# Microcontroller.net
KiCad netlist of a schematic drawn in Altium Designer
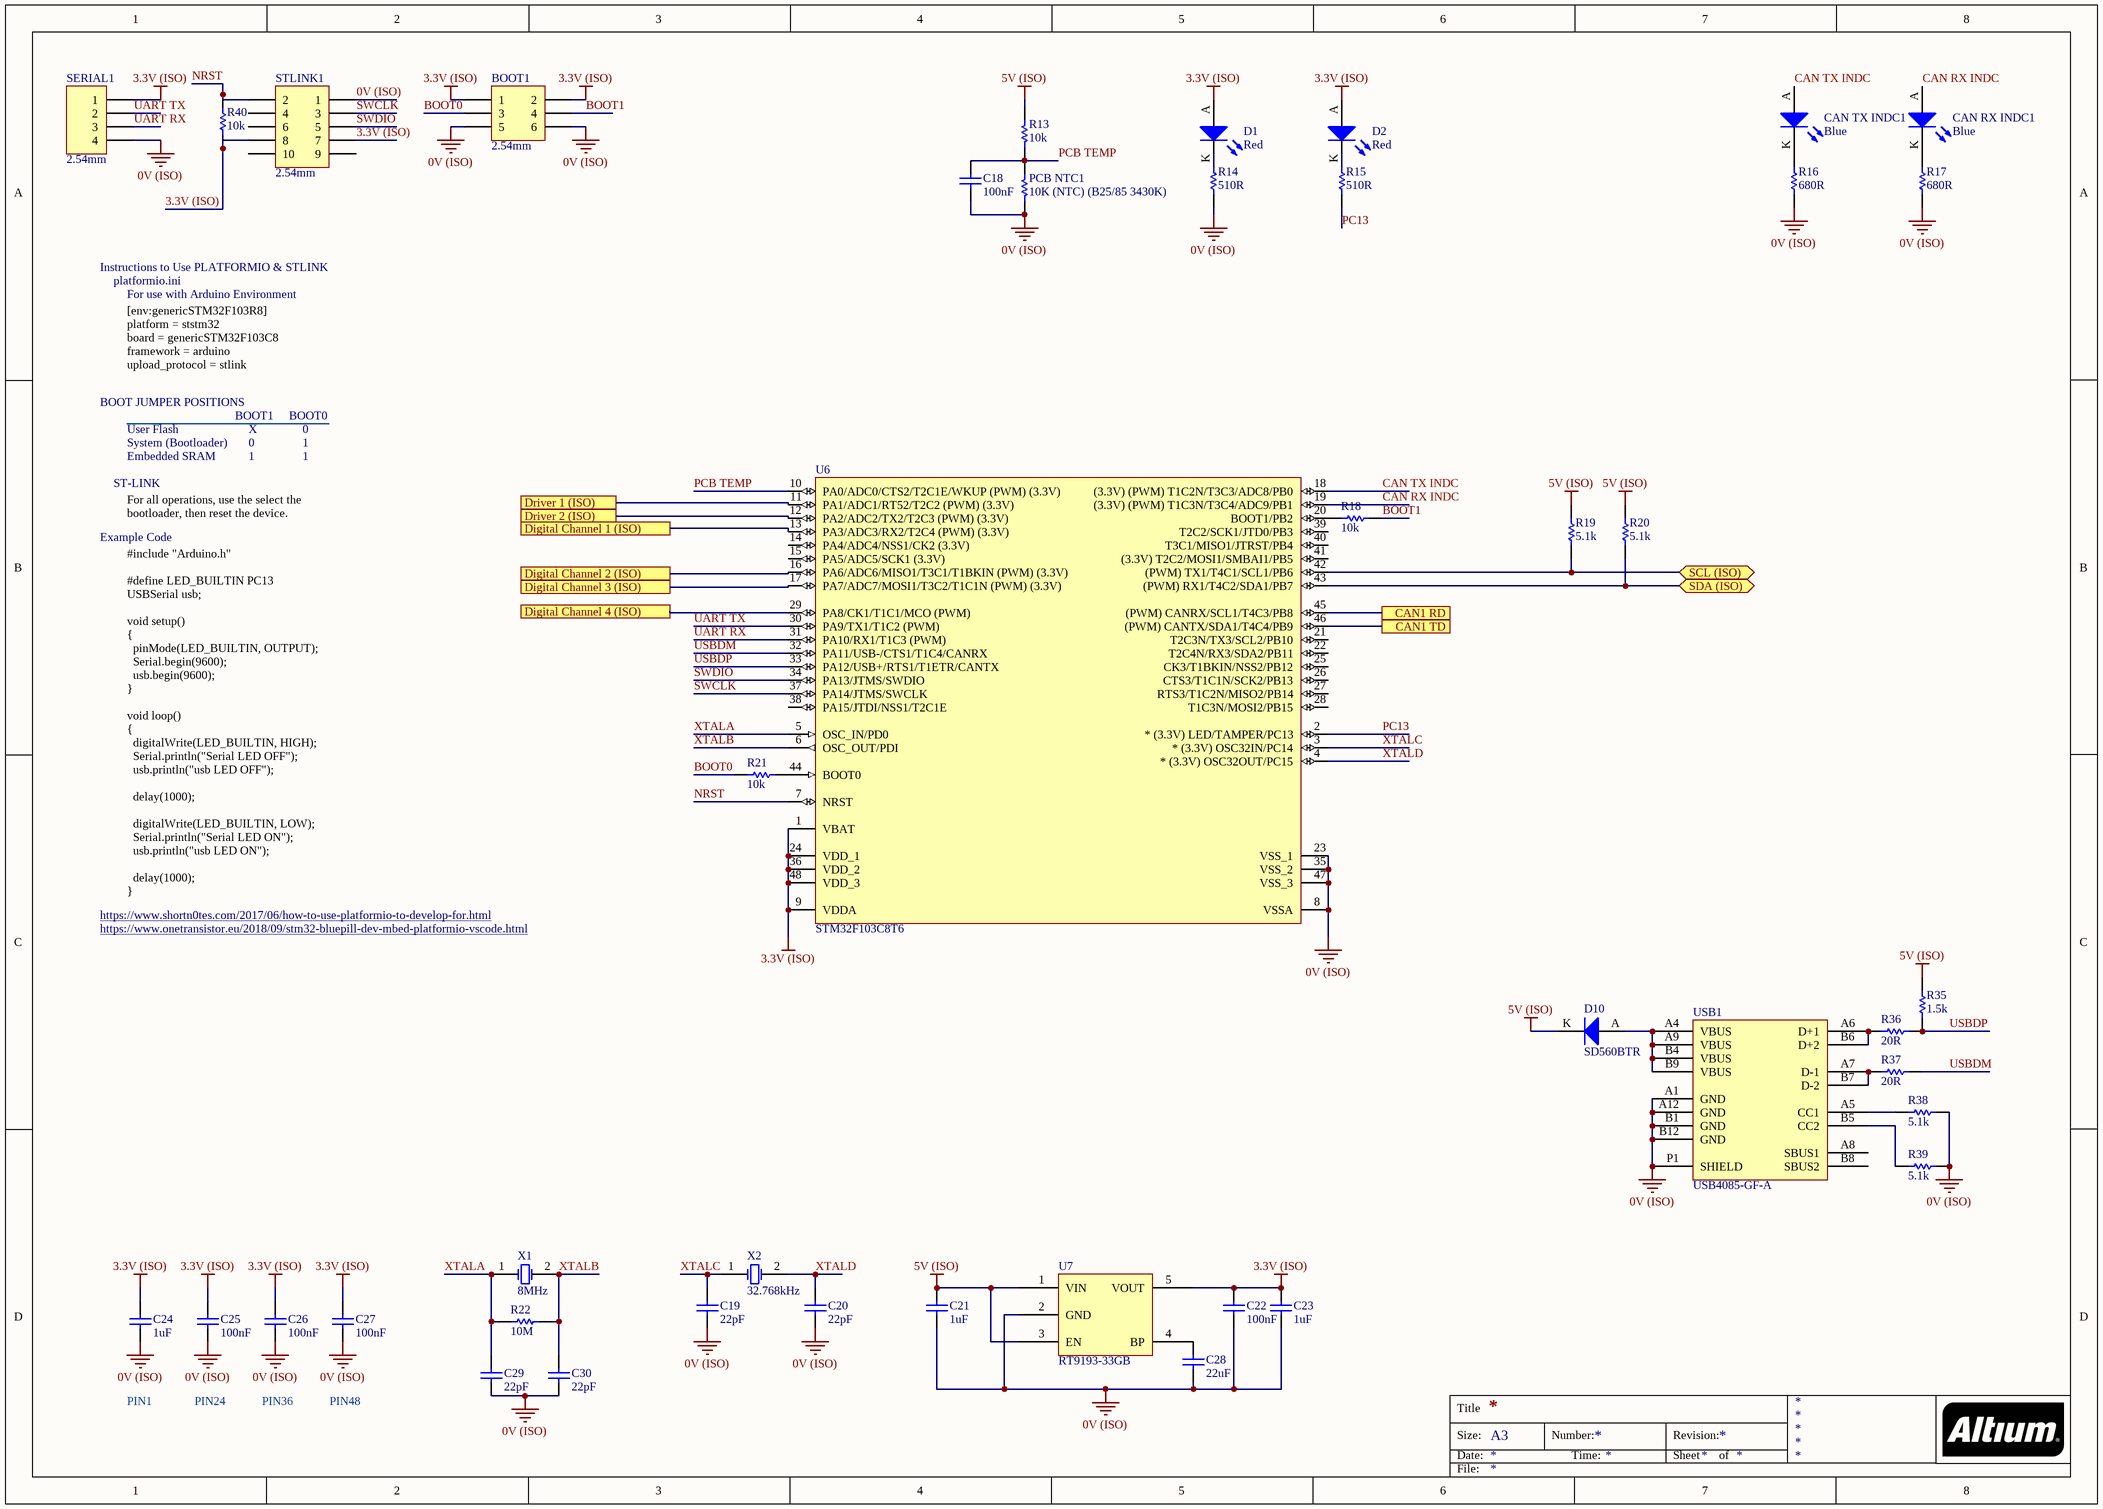
[diagram p0: Microcontroller.SchDoc]

(export (version "E")
  (design (tool "Eeschema 10.0.6"))
  (components
    (comp (ref "BOOT1")
      (value "2.54mm")
      (footprint "TH 2.54mm Header 2x3")
      (fields (field (name "PART NUMBER") "TH 2.54mm Header 2x3") (field (name "CONTACT") "NA"))
      (libsource (lib "ts_20-standard-connectors") (part "Header 2x3"))
    )
    (comp (ref "C18")
      (value "100nF")
      (footprint "0805")
      (fields
        (field (name "PART NUMBER") "GCM21BR71E104KA37L")
        (field (name "TOLERANCE") "10%")
        (field (name "MANUFACTURER") "muRata")
      )
      (libsource (lib "ts_20-standard-library") (part "Capacitor"))
    )
    (comp (ref "C19")
      (value "22pF")
      (footprint "0805")
      (fields
        (field (name "PART NUMBER") "GCM21B5C1H220JA37L")
        (field (name "TOLERANCE") "5%")
        (field (name "MANUFACTURER") "muRata")
      )
      (libsource (lib "ts_20-standard-library") (part "Capacitor"))
    )
    (comp (ref "C20")
      (value "22pF")
      (footprint "0805")
      (fields
        (field (name "PART NUMBER") "GCM21B5C1H220JA37L")
        (field (name "TOLERANCE") "5%")
        (field (name "MANUFACTURER") "muRata")
      )
      (libsource (lib "ts_20-standard-library") (part "Capacitor"))
    )
    (comp (ref "C21")
      (value "1uF")
      (footprint "0805")
      (fields
        (field (name "PART NUMBER") "AC0805KKX7R8BB105")
        (field (name "TOLERANCE") "10%")
        (field (name "MANUFACTURER") "YAGEO")
      )
      (libsource (lib "ts_20-standard-library") (part "Capacitor"))
    )
    (comp (ref "C22")
      (value "100nF")
      (footprint "0805")
      (fields
        (field (name "PART NUMBER") "GCM21BR71E104KA37L")
        (field (name "TOLERANCE") "10%")
        (field (name "MANUFACTURER") "muRata")
      )
      (libsource (lib "ts_20-standard-library") (part "Capacitor"))
    )
    (comp (ref "C23")
      (value "1uF")
      (footprint "0805")
      (fields
        (field (name "PART NUMBER") "AC0805KKX7R8BB105")
        (field (name "TOLERANCE") "10%")
        (field (name "MANUFACTURER") "YAGEO")
      )
      (libsource (lib "ts_20-standard-library") (part "Capacitor"))
    )
    (comp (ref "C24")
      (value "1uF")
      (footprint "0805")
      (fields
        (field (name "PART NUMBER") "AC0805KKX7R8BB105")
        (field (name "TOLERANCE") "10%")
        (field (name "MANUFACTURER") "YAGEO")
      )
      (libsource (lib "ts_20-standard-library") (part "Capacitor"))
    )
    (comp (ref "C25")
      (value "100nF")
      (footprint "0805")
      (fields
        (field (name "PART NUMBER") "GCM21BR71E104KA37L")
        (field (name "TOLERANCE") "10%")
        (field (name "MANUFACTURER") "muRata")
      )
      (libsource (lib "ts_20-standard-library") (part "Capacitor"))
    )
    (comp (ref "C26")
      (value "100nF")
      (footprint "0805")
      (fields
        (field (name "PART NUMBER") "GCM21BR71E104KA37L")
        (field (name "TOLERANCE") "10%")
        (field (name "MANUFACTURER") "muRata")
      )
      (libsource (lib "ts_20-standard-library") (part "Capacitor"))
    )
    (comp (ref "C27")
      (value "100nF")
      (footprint "0805")
      (fields
        (field (name "PART NUMBER") "GCM21BR71E104KA37L")
        (field (name "TOLERANCE") "10%")
        (field (name "MANUFACTURER") "muRata")
      )
      (libsource (lib "ts_20-standard-library") (part "Capacitor"))
    )
    (comp (ref "C28")
      (value "22uF")
      (footprint "0805")
      (fields
        (field (name "PART NUMBER") "GRM21BR61A226ME51L")
        (field (name "TOLERANCE") "20%")
        (field (name "MANUFACTURER") "muRata")
      )
      (libsource (lib "ts_20-standard-library") (part "Capacitor"))
    )
    (comp (ref "C29")
      (value "22pF")
      (footprint "0805")
      (fields
        (field (name "PART NUMBER") "GCM21B5C1H220JA37L")
        (field (name "TOLERANCE") "5%")
        (field (name "MANUFACTURER") "muRata")
      )
      (libsource (lib "ts_20-standard-library") (part "Capacitor"))
    )
    (comp (ref "C30")
      (value "22pF")
      (footprint "0805")
      (fields
        (field (name "PART NUMBER") "GCM21B5C1H220JA37L")
        (field (name "TOLERANCE") "5%")
        (field (name "MANUFACTURER") "muRata")
      )
      (libsource (lib "ts_20-standard-library") (part "Capacitor"))
    )
    (comp (ref "CAN RX INDC1")
      (value "Blue")
      (footprint "0805 LED")
      (description "LED BLUE CLEAR 2012 SMD")
      (fields
        (field (name "PART NUMBER") "SML-MN2BCTT86C")
        (field (name "MANUFACTURER") "ROHM Semiconductor")
      )
      (libsource (lib "ts_20-standard-library") (part "LED"))
    )
    (comp (ref "CAN TX INDC1")
      (value "Blue")
      (footprint "0805 LED")
      (description "LED BLUE CLEAR 2012 SMD")
      (fields
        (field (name "PART NUMBER") "SML-MN2BCTT86C")
        (field (name "MANUFACTURER") "ROHM Semiconductor")
      )
      (libsource (lib "ts_20-standard-library") (part "LED"))
    )
    (comp (ref "D1")
      (value "Red")
      (footprint "0805 LED")
      (description "Red LED Indication - Discrete 1.75V 0805 (2012 Metric)")
      (fields (field (name "MANUFACTURER") "ROHM Semiconductor") (field (name "PART NUMBER") "SML-210LTT86"))
      (libsource (lib "ts_20-standard-library") (part "LED"))
    )
    (comp (ref "D2")
      (value "Red")
      (footprint "0805 LED")
      (description "Red LED Indication - Discrete 1.75V 0805 (2012 Metric)")
      (fields (field (name "MANUFACTURER") "ROHM Semiconductor") (field (name "PART NUMBER") "SML-210LTT86"))
      (libsource (lib "ts_20-standard-library") (part "LED"))
    )
    (comp (ref "D10")
      (value "SD560BTR")
      (footprint "SMB Diode")
      (description "1.2V_F 600V 5A SMB")
      (fields
        (field (name "MANUFACTURER") "SMC Diode Solutions")
        (field (name "DIGIKEY PART NUMBER") "1655-1530-2-ND")
      )
      (libsource (lib "ts_20-standard-library") (part "Diode"))
    )
    (comp (ref "PCB NTC1")
      (value "10K (NTC) (B25/85 3430K)")
      (footprint "0805")
      (fields
        (field (name "PART NUMBER") "NTCS0805E3103FLT")
        (field (name "MANUFACTURER") "Vishay Beyschlag")
        (field (name "TOLERANCE") "0.01")
      )
      (libsource (lib "ts_20-standard-library") (part "Resistor"))
    )
    (comp (ref "R13")
      (value "10k")
      (footprint "0805")
      (fields
        (field (name "PART NUMBER") "RC0805FR0710KL")
        (field (name "MANUFACTURER") "YAGEO")
        (field (name "TOLERANCE") "0.01")
      )
      (libsource (lib "ts_20-standard-library") (part "Resistor"))
    )
    (comp (ref "R14")
      (value "510R")
      (footprint "0805")
      (fields
        (field (name "MANUFACTURER") "YAGEO")
        (field (name "PART NUMBER") "RC0805FR07510RL")
        (field (name "TOLERANCE") "0.01")
      )
      (libsource (lib "ts_20-standard-library") (part "Resistor"))
    )
    (comp (ref "R15")
      (value "510R")
      (footprint "0805")
      (fields
        (field (name "MANUFACTURER") "YAGEO")
        (field (name "PART NUMBER") "RC0805FR07510RL")
        (field (name "TOLERANCE") "0.01")
      )
      (libsource (lib "ts_20-standard-library") (part "Resistor"))
    )
    (comp (ref "R16")
      (value "680R")
      (footprint "0805")
      (fields
        (field (name "PART NUMBER") "RC0805FR07680RL")
        (field (name "MANUFACTURER") "YAGEO")
        (field (name "TOLERANCE") "0.01")
      )
      (libsource (lib "ts_20-standard-library") (part "Resistor"))
    )
    (comp (ref "R17")
      (value "680R")
      (footprint "0805")
      (fields
        (field (name "PART NUMBER") "RC0805FR07680RL")
        (field (name "MANUFACTURER") "YAGEO")
        (field (name "TOLERANCE") "0.01")
      )
      (libsource (lib "ts_20-standard-library") (part "Resistor"))
    )
    (comp (ref "R18")
      (value "10k")
      (footprint "0805")
      (fields
        (field (name "PART NUMBER") "RC0805FR0710KL")
        (field (name "MANUFACTURER") "YAGEO")
        (field (name "TOLERANCE") "0.01")
      )
      (libsource (lib "ts_20-standard-library") (part "Resistor"))
    )
    (comp (ref "R19")
      (value "5.1k")
      (footprint "0805")
      (fields
        (field (name "PART NUMBER") "RC0805FR075K1L")
        (field (name "MANUFACTURER") "YAGEO")
        (field (name "TOLERANCE") "0.01")
      )
      (libsource (lib "ts_20-standard-library") (part "Resistor"))
    )
    (comp (ref "R20")
      (value "5.1k")
      (footprint "0805")
      (fields
        (field (name "PART NUMBER") "RC0805FR075K1L")
        (field (name "MANUFACTURER") "YAGEO")
        (field (name "TOLERANCE") "0.01")
      )
      (libsource (lib "ts_20-standard-library") (part "Resistor"))
    )
    (comp (ref "R21")
      (value "10k")
      (footprint "0805")
      (fields
        (field (name "PART NUMBER") "RC0805FR0710KL")
        (field (name "MANUFACTURER") "YAGEO")
        (field (name "TOLERANCE") "0.01")
      )
      (libsource (lib "ts_20-standard-library") (part "Resistor"))
    )
    (comp (ref "R22")
      (value "10M")
      (footprint "0805")
      (fields
        (field (name "PART NUMBER") "RC0805FR0710ML")
        (field (name "MANUFACTURER") "YAGEO")
        (field (name "TOLERANCE") "0.01")
      )
      (libsource (lib "ts_20-standard-library") (part "Resistor"))
    )
    (comp (ref "R35")
      (value "1.5k")
      (footprint "0805")
      (fields
        (field (name "PART NUMBER") "RC0805FR071K5L")
        (field (name "MANUFACTURER") "YAGEO")
        (field (name "TOLERANCE") "0.01")
      )
      (libsource (lib "ts_20-standard-library") (part "Resistor"))
    )
    (comp (ref "R36")
      (value "20R")
      (footprint "0805")
      (fields
        (field (name "PART NUMBER") "RC0805FR0720RL")
        (field (name "MANUFACTURER") "YAGEO")
        (field (name "TOLERANCE") "0.01")
      )
      (libsource (lib "ts_20-standard-library") (part "Resistor"))
    )
    (comp (ref "R37")
      (value "20R")
      (footprint "0805")
      (fields
        (field (name "PART NUMBER") "RC0805FR0720RL")
        (field (name "MANUFACTURER") "YAGEO")
        (field (name "TOLERANCE") "0.01")
      )
      (libsource (lib "ts_20-standard-library") (part "Resistor"))
    )
    (comp (ref "R38")
      (value "5.1k")
      (footprint "0805")
      (fields
        (field (name "PART NUMBER") "RC0805FR075K1L")
        (field (name "MANUFACTURER") "YAGEO")
        (field (name "TOLERANCE") "0.01")
      )
      (libsource (lib "ts_20-standard-library") (part "Resistor"))
    )
    (comp (ref "R39")
      (value "5.1k")
      (footprint "0805")
      (fields
        (field (name "PART NUMBER") "RC0805FR075K1L")
        (field (name "MANUFACTURER") "YAGEO")
        (field (name "TOLERANCE") "0.01")
      )
      (libsource (lib "ts_20-standard-library") (part "Resistor"))
    )
    (comp (ref "R40")
      (value "10k")
      (footprint "0805")
      (fields
        (field (name "PART NUMBER") "RC0805FR0710KL")
        (field (name "MANUFACTURER") "YAGEO")
        (field (name "TOLERANCE") "0.01")
      )
      (libsource (lib "ts_20-standard-library") (part "Resistor"))
    )
    (comp (ref "SERIAL1")
      (value "2.54mm")
      (footprint "TH 2.54mm Header 1x4")
      (fields (field (name "PART NUMBER") "TH 2.54mm Header 1x4") (field (name "CONTACT") "NA"))
      (libsource (lib "ts_20-standard-connectors") (part "Header 1x4"))
    )
    (comp (ref "STLINK1")
      (value "2.54mm")
      (footprint "TH 2.54mm Header 2x5")
      (fields (field (name "PART NUMBER") "TH 2.54mm Header 2x5") (field (name "CONTACT") "NA"))
      (libsource (lib "ts_20-standard-connectors") (part "Header 2x5"))
    )
    (comp (ref "U6")
      (value "STM32F103C8T6")
      (footprint "STM 48-LQFP")
      (description "ARM® Cortex®-M3 STM32F1 Microcontroller IC 32-Bit 72MHz 64KB (64K x 8) FLASH")
      (fields
        (field (name "MANUFACTURER") "STMicroelectronics")
        (field (name "DIGIKEY PART NUMBER") "497-6063-ND")
      )
      (libsource (lib "ts_20-standard-library") (part "STM32F103C8T6"))
    )
    (comp (ref "U7")
      (value "RT9193-33GB")
      (footprint "RICHTEK SOT-23-5")
      (description "IC REG LINEAR 3.3V 300MA SOT23-5")
      (fields (field (name "MANUFACTURER") "Richtek") (field (name "DIGIKEY PART NUMBER") "1028-1014-1-ND"))
      (libsource (lib "ts_20-standard-library") (part "RT9193-33GB"))
    )
    (comp (ref "USB1")
      (value "USB4085-GF-A")
      (footprint "USB4085-GF-A")
      (description "USB - C (Type - C) USB 2.0 Receptacle Connector 16 Position Through Hole, Right Angle")
      (fields (field (name "DIGIKEY PART NUMBER") "2073-USB4085-GF-ACT-ND"))
      (libsource (lib "ts_20-standard-connectors") (part "USB4085-GF-A"))
    )
    (comp (ref "X1")
      (value "8MHz")
      (footprint "Abracon HC-49/US")
      (fields
        (field (name "PART NUMBER") "ABLS-8.000MHZ-B4-T")
        (field (name "MANUFACTURER") "Abracon LLC")
        (field (name "DIGIKEY PART NUMBER") "535-10212-2-ND")
      )
      (libsource (lib "ts_20-standard-library") (part "Crystal"))
    )
    (comp (ref "X2")
      (value "32.768kHz")
      (footprint "EPSON 2-SMD")
      (fields
        (field (name "PART NUMBER") "FC-135 32.7680KA-A5")
        (field (name "MANUFACTURER") "EPSON")
        (field (name "DIGIKEY PART NUMBER") "SER4103TR-ND")
      )
      (libsource (lib "ts_20-standard-library") (part "Crystal"))
    )
  )
  (nets
    (net (code "1") (name "/BOOT0") (class "Default")
      (node (ref "BOOT1") (pin "3") (pinfunction "3_3") (pintype "passive"))
      (node (ref "R21") (pin "1") (pinfunction "1_1") (pintype "passive"))
    )
    (net (code "2") (name "/BOOT1") (class "Default")
      (node (ref "BOOT1") (pin "4") (pinfunction "4_4") (pintype "passive"))
      (node (ref "R18") (pin "2") (pinfunction "2_2") (pintype "passive"))
    )
    (net (code "3") (name "/CAN RX INDC") (class "Default")
      (node (ref "CAN RX INDC1") (pin "A") (pinfunction "A_A") (pintype "passive"))
      (node (ref "U6") (pin "19") (pinfunction "(3.3V)_(PWM)_T1C3N/T3C4/ADC9/PB1_19") (pintype "bidirectional"))
    )
    (net (code "4") (name "/CAN TX INDC") (class "Default")
      (node (ref "CAN TX INDC1") (pin "A") (pinfunction "A_A") (pintype "passive"))
      (node (ref "U6") (pin "18") (pinfunction "(3.3V)_(PWM)_T1C2N/T3C3/ADC8/PB0_18") (pintype "bidirectional"))
    )
    (net (code "5") (name "/CAN1 RD") (class "Default")
      (node (ref "U6") (pin "45") (pinfunction "(PWM)_CANRX/SCL1/T4C3/PB8_45") (pintype "bidirectional"))
    )
    (net (code "6") (name "/CAN1 TD") (class "Default")
      (node (ref "U6") (pin "46") (pinfunction "(PWM)_CANTX/SDA1/T4C4/PB9_46") (pintype "bidirectional"))
    )
    (net (code "7") (name "/Digital Channel 1 (ISO)") (class "Default")
      (node (ref "U6") (pin "13") (pinfunction "PA3/ADC3/RX2/T2C4_(PWM)_(3.3V)_13") (pintype "bidirectional"))
    )
    (net (code "8") (name "/Digital Channel 2 (ISO)") (class "Default")
      (node (ref "U6") (pin "16") (pinfunction "PA6/ADC6/MISO1/T3C1/T1BKIN_(PWM)_(3.3V)_16") (pintype "bidirectional"))
    )
    (net (code "9") (name "/Digital Channel 3 (ISO)") (class "Default")
      (node (ref "U6") (pin "17") (pinfunction "PA7/ADC7/MOSI1/T3C2/T1C1N_(PWM)_(3.3V)_17") (pintype "bidirectional"))
    )
    (net (code "10") (name "/Digital Channel 4 (ISO)") (class "Default")
      (node (ref "U6") (pin "29") (pinfunction "PA8/CK1/T1C1/MCO_(PWM)_29") (pintype "bidirectional"))
    )
    (net (code "11") (name "/Driver 1 (ISO)") (class "Default")
      (node (ref "U6") (pin "11") (pinfunction "PA1/ADC1/RT52/T2C2_(PWM)_(3.3V)_11") (pintype "bidirectional"))
    )
    (net (code "12") (name "/Driver 2 (ISO)") (class "Default")
      (node (ref "U6") (pin "12") (pinfunction "PA2/ADC2/TX2/T2C3_(PWM)_(3.3V)_12") (pintype "bidirectional"))
    )
    (net (code "13") (name "/NRST") (class "Default")
      (node (ref "R40") (pin "2") (pinfunction "2_2") (pintype "passive"))
      (node (ref "STLINK1") (pin "2") (pinfunction "2_2") (pintype "passive"))
      (node (ref "U6") (pin "7") (pinfunction "NRST_7") (pintype "bidirectional"))
    )
    (net (code "14") (name "/PC13") (class "Default")
      (node (ref "R15") (pin "1") (pinfunction "1_1") (pintype "passive"))
      (node (ref "U6") (pin "2") (pinfunction "*_(3.3V)_LED/TAMPER/PC13_2") (pintype "bidirectional"))
    )
    (net (code "15") (name "/PCB TEMP") (class "Default")
      (node (ref "C18") (pin "2") (pinfunction "2_2") (pintype "passive"))
      (node (ref "PCB NTC1") (pin "2") (pinfunction "2_2") (pintype "passive"))
      (node (ref "R13") (pin "1") (pinfunction "1_1") (pintype "passive"))
      (node (ref "U6") (pin "10") (pinfunction "PA0/ADC0/CTS2/T2C1E/WKUP_(PWM)_(3.3V)_10") (pintype "bidirectional"))
    )
    (net (code "16") (name "/SCL (ISO)") (class "Default")
      (node (ref "R19") (pin "1") (pinfunction "1_1") (pintype "passive"))
      (node (ref "U6") (pin "42") (pinfunction "(PWM)_TX1/T4C1/SCL1/PB6_42") (pintype "bidirectional"))
    )
    (net (code "17") (name "/SDA (ISO)") (class "Default")
      (node (ref "R20") (pin "1") (pinfunction "1_1") (pintype "passive"))
      (node (ref "U6") (pin "43") (pinfunction "(PWM)_RX1/T4C2/SDA1/PB7_43") (pintype "bidirectional"))
    )
    (net (code "18") (name "/SWCLK") (class "Default")
      (node (ref "STLINK1") (pin "3") (pinfunction "3_3") (pintype "passive"))
      (node (ref "U6") (pin "37") (pinfunction "PA14/JTMS/SWCLK_37") (pintype "bidirectional"))
    )
    (net (code "19") (name "/SWDIO") (class "Default")
      (node (ref "STLINK1") (pin "5") (pinfunction "5_5") (pintype "passive"))
      (node (ref "U6") (pin "34") (pinfunction "PA13/JTMS/SWDIO_34") (pintype "bidirectional"))
    )
    (net (code "20") (name "/UART RX") (class "Default")
      (node (ref "SERIAL1") (pin "3") (pinfunction "3_3") (pintype "passive"))
      (node (ref "U6") (pin "31") (pinfunction "PA10/RX1/T1C3_(PWM)_31") (pintype "bidirectional"))
    )
    (net (code "21") (name "/UART TX") (class "Default")
      (node (ref "SERIAL1") (pin "2") (pinfunction "2_2") (pintype "passive"))
      (node (ref "U6") (pin "30") (pinfunction "PA9/TX1/T1C2_(PWM)_30") (pintype "bidirectional"))
    )
    (net (code "22") (name "/USBDM") (class "Default")
      (node (ref "R37") (pin "2") (pinfunction "2_2") (pintype "passive"))
      (node (ref "U6") (pin "32") (pinfunction "PA11/USB-/CTS1/T1C4/CANRX_32") (pintype "bidirectional"))
    )
    (net (code "23") (name "/USBDP") (class "Default")
      (node (ref "R35") (pin "1") (pinfunction "1_1") (pintype "passive"))
      (node (ref "R36") (pin "2") (pinfunction "2_2") (pintype "passive"))
      (node (ref "U6") (pin "33") (pinfunction "PA12/USB+/RTS1/T1ETR/CANTX_33") (pintype "bidirectional"))
    )
    (net (code "24") (name "/XTALA") (class "Default")
      (node (ref "C29") (pin "2") (pinfunction "2_2") (pintype "passive"))
      (node (ref "R22") (pin "2") (pinfunction "2_2") (pintype "passive"))
      (node (ref "U6") (pin "5") (pinfunction "OSC_IN/PD0_5") (pintype "input"))
      (node (ref "X1") (pin "1") (pinfunction "OSC1_1") (pintype "passive"))
    )
    (net (code "25") (name "/XTALB") (class "Default")
      (node (ref "C30") (pin "2") (pinfunction "2_2") (pintype "passive"))
      (node (ref "R22") (pin "1") (pinfunction "1_1") (pintype "passive"))
      (node (ref "U6") (pin "6") (pinfunction "OSC_OUT/PDI_6") (pintype "output"))
      (node (ref "X1") (pin "2") (pinfunction "OSC2_2") (pintype "passive"))
    )
    (net (code "26") (name "/XTALC") (class "Default")
      (node (ref "C19") (pin "2") (pinfunction "2_2") (pintype "passive"))
      (node (ref "U6") (pin "3") (pinfunction "*_(3.3V)_OSC32IN/PC14_3") (pintype "bidirectional"))
      (node (ref "X2") (pin "1") (pinfunction "OSC1_1") (pintype "passive"))
    )
    (net (code "27") (name "/XTALD") (class "Default")
      (node (ref "C20") (pin "2") (pinfunction "2_2") (pintype "passive"))
      (node (ref "U6") (pin "4") (pinfunction "*_(3.3V)_OSC32OUT/PC15_4") (pintype "bidirectional"))
      (node (ref "X2") (pin "2") (pinfunction "OSC2_2") (pintype "passive"))
    )
    (net (code "28") (name "0V (ISO)") (class "Default")
      (node (ref "BOOT1") (pin "5") (pinfunction "5_5") (pintype "passive"))
      (node (ref "BOOT1") (pin "6") (pinfunction "6_6") (pintype "passive"))
      (node (ref "C18") (pin "1") (pinfunction "1_1") (pintype "passive"))
      (node (ref "C19") (pin "1") (pinfunction "1_1") (pintype "passive"))
      (node (ref "C20") (pin "1") (pinfunction "1_1") (pintype "passive"))
      (node (ref "C21") (pin "1") (pinfunction "1_1") (pintype "passive"))
      (node (ref "C22") (pin "1") (pinfunction "1_1") (pintype "passive"))
      (node (ref "C23") (pin "1") (pinfunction "1_1") (pintype "passive"))
      (node (ref "C24") (pin "1") (pinfunction "1_1") (pintype "passive"))
      (node (ref "C25") (pin "1") (pinfunction "1_1") (pintype "passive"))
      (node (ref "C26") (pin "1") (pinfunction "1_1") (pintype "passive"))
      (node (ref "C27") (pin "1") (pinfunction "1_1") (pintype "passive"))
      (node (ref "C28") (pin "1") (pinfunction "1_1") (pintype "passive"))
      (node (ref "C29") (pin "1") (pinfunction "1_1") (pintype "passive"))
      (node (ref "C30") (pin "1") (pinfunction "1_1") (pintype "passive"))
      (node (ref "PCB NTC1") (pin "1") (pinfunction "1_1") (pintype "passive"))
      (node (ref "R14") (pin "1") (pinfunction "1_1") (pintype "passive"))
      (node (ref "R16") (pin "1") (pinfunction "1_1") (pintype "passive"))
      (node (ref "R17") (pin "1") (pinfunction "1_1") (pintype "passive"))
      (node (ref "R38") (pin "2") (pinfunction "2_2") (pintype "passive"))
      (node (ref "R39") (pin "2") (pinfunction "2_2") (pintype "passive"))
      (node (ref "SERIAL1") (pin "4") (pinfunction "4_4") (pintype "passive"))
      (node (ref "STLINK1") (pin "1") (pinfunction "1_1") (pintype "passive"))
      (node (ref "U6") (pin "23") (pinfunction "VSS_1_23") (pintype "power_in"))
      (node (ref "U6") (pin "35") (pinfunction "VSS_2_35") (pintype "power_in"))
      (node (ref "U6") (pin "47") (pinfunction "VSS_3_47") (pintype "power_in"))
      (node (ref "U6") (pin "8") (pinfunction "VSSA_8") (pintype "power_in"))
      (node (ref "U7") (pin "2") (pinfunction "GND_2") (pintype "passive"))
      (node (ref "USB1") (pin "A1") (pinfunction "GND_A1") (pintype "passive"))
      (node (ref "USB1") (pin "A12") (pinfunction "GND_A12") (pintype "passive"))
      (node (ref "USB1") (pin "B1") (pinfunction "GND_B1") (pintype "passive"))
      (node (ref "USB1") (pin "B12") (pinfunction "GND_B12") (pintype "passive"))
      (node (ref "USB1") (pin "P1") (pinfunction "SHIELD_P1") (pintype "passive"))
    )
    (net (code "29") (name "3.3V (ISO)") (class "Default")
      (node (ref "BOOT1") (pin "1") (pinfunction "1_1") (pintype "passive"))
      (node (ref "BOOT1") (pin "2") (pinfunction "2_2") (pintype "passive"))
      (node (ref "C22") (pin "2") (pinfunction "2_2") (pintype "passive"))
      (node (ref "C23") (pin "2") (pinfunction "2_2") (pintype "passive"))
      (node (ref "C24") (pin "2") (pinfunction "2_2") (pintype "passive"))
      (node (ref "C25") (pin "2") (pinfunction "2_2") (pintype "passive"))
      (node (ref "C26") (pin "2") (pinfunction "2_2") (pintype "passive"))
      (node (ref "C27") (pin "2") (pinfunction "2_2") (pintype "passive"))
      (node (ref "D1") (pin "A") (pinfunction "A_A") (pintype "passive"))
      (node (ref "D2") (pin "A") (pinfunction "A_A") (pintype "passive"))
      (node (ref "R40") (pin "1") (pinfunction "1_1") (pintype "passive"))
      (node (ref "SERIAL1") (pin "1") (pinfunction "1_1") (pintype "passive"))
      (node (ref "STLINK1") (pin "7") (pinfunction "7_7") (pintype "passive"))
      (node (ref "STLINK1") (pin "8") (pinfunction "8_8") (pintype "passive"))
      (node (ref "U6") (pin "1") (pinfunction "VBAT_1") (pintype "power_in"))
      (node (ref "U6") (pin "24") (pinfunction "VDD_1_24") (pintype "power_in"))
      (node (ref "U6") (pin "36") (pinfunction "VDD_2_36") (pintype "power_in"))
      (node (ref "U6") (pin "48") (pinfunction "VDD_3_48") (pintype "power_in"))
      (node (ref "U6") (pin "9") (pinfunction "VDDA_9") (pintype "power_in"))
      (node (ref "U7") (pin "5") (pinfunction "VOUT_5") (pintype "passive"))
    )
    (net (code "30") (name "5V (ISO)") (class "Default")
      (node (ref "C21") (pin "2") (pinfunction "2_2") (pintype "passive"))
      (node (ref "D10") (pin "K") (pinfunction "K_K") (pintype "passive"))
      (node (ref "R13") (pin "2") (pinfunction "2_2") (pintype "passive"))
      (node (ref "R19") (pin "2") (pinfunction "2_2") (pintype "passive"))
      (node (ref "R20") (pin "2") (pinfunction "2_2") (pintype "passive"))
      (node (ref "R35") (pin "2") (pinfunction "2_2") (pintype "passive"))
      (node (ref "U7") (pin "1") (pinfunction "VIN_1") (pintype "passive"))
      (node (ref "U7") (pin "3") (pinfunction "EN_3") (pintype "passive"))
    )
    (net (code "31") (name "Net-(CAN RX INDC1-PadK)") (class "Default")
      (node (ref "CAN RX INDC1") (pin "K") (pinfunction "K_K") (pintype "passive"))
      (node (ref "R17") (pin "2") (pinfunction "2_2") (pintype "passive"))
    )
    (net (code "32") (name "Net-(CAN TX INDC1-PadK)") (class "Default")
      (node (ref "CAN TX INDC1") (pin "K") (pinfunction "K_K") (pintype "passive"))
      (node (ref "R16") (pin "2") (pinfunction "2_2") (pintype "passive"))
    )
    (net (code "33") (name "Net-(D1-PadK)") (class "Default")
      (node (ref "D1") (pin "K") (pinfunction "K_K") (pintype "passive"))
      (node (ref "R14") (pin "2") (pinfunction "2_2") (pintype "passive"))
    )
    (net (code "34") (name "Net-(D2-PadK)") (class "Default")
      (node (ref "D2") (pin "K") (pinfunction "K_K") (pintype "passive"))
      (node (ref "R15") (pin "2") (pinfunction "2_2") (pintype "passive"))
    )
    (net (code "35") (name "Net-(D10-PadA)") (class "Default")
      (node (ref "D10") (pin "A") (pinfunction "A_A") (pintype "passive"))
      (node (ref "USB1") (pin "A4") (pinfunction "VBUS_A4") (pintype "passive"))
      (node (ref "USB1") (pin "A9") (pinfunction "VBUS_A9") (pintype "passive"))
      (node (ref "USB1") (pin "B4") (pinfunction "VBUS_B4") (pintype "passive"))
      (node (ref "USB1") (pin "B9") (pinfunction "VBUS_B9") (pintype "passive"))
    )
    (net (code "36") (name "Net-(U6-BOOT0)") (class "Default")
      (node (ref "R21") (pin "2") (pinfunction "2_2") (pintype "passive"))
      (node (ref "U6") (pin "44") (pinfunction "BOOT0_44") (pintype "input"))
    )
    (net (code "37") (name "Net-(U6-BOOT1{slash}PB2)") (class "Default")
      (node (ref "R18") (pin "1") (pinfunction "1_1") (pintype "passive"))
      (node (ref "U6") (pin "20") (pinfunction "BOOT1/PB2_20") (pintype "bidirectional"))
    )
    (net (code "38") (name "Net-(U7-BP)") (class "Default")
      (node (ref "C28") (pin "2") (pinfunction "2_2") (pintype "passive"))
      (node (ref "U7") (pin "4") (pinfunction "BP_4") (pintype "passive"))
    )
    (net (code "39") (name "Net-(USB1-CC1)") (class "Default")
      (node (ref "R38") (pin "1") (pinfunction "1_1") (pintype "passive"))
      (node (ref "USB1") (pin "A5") (pinfunction "CC1_A5") (pintype "passive"))
    )
    (net (code "40") (name "Net-(USB1-CC2)") (class "Default")
      (node (ref "R39") (pin "1") (pinfunction "1_1") (pintype "passive"))
      (node (ref "USB1") (pin "B5") (pinfunction "CC2_B5") (pintype "passive"))
    )
    (net (code "41") (name "Net-(USB1-D+1)") (class "Default")
      (node (ref "R36") (pin "1") (pinfunction "1_1") (pintype "passive"))
      (node (ref "USB1") (pin "A6") (pinfunction "D+1_A6") (pintype "passive"))
      (node (ref "USB1") (pin "B6") (pinfunction "D+2_B6") (pintype "passive"))
    )
    (net (code "42") (name "Net-(USB1-D-1)") (class "Default")
      (node (ref "R37") (pin "1") (pinfunction "1_1") (pintype "passive"))
      (node (ref "USB1") (pin "A7") (pinfunction "D-1_A7") (pintype "passive"))
      (node (ref "USB1") (pin "B7") (pinfunction "D-2_B7") (pintype "passive"))
    )
    (net (code "43") (name "unconnected-(STLINK1-Pad4)") (class "Default")
      (node (ref "STLINK1") (pin "4") (pinfunction "4_4") (pintype "passive"))
    )
    (net (code "44") (name "unconnected-(STLINK1-Pad6)") (class "Default")
      (node (ref "STLINK1") (pin "6") (pinfunction "6_6") (pintype "passive"))
    )
    (net (code "45") (name "unconnected-(STLINK1-Pad9)") (class "Default")
      (node (ref "STLINK1") (pin "9") (pinfunction "9_9") (pintype "passive"))
    )
    (net (code "46") (name "unconnected-(STLINK1-Pad10)") (class "Default")
      (node (ref "STLINK1") (pin "10") (pinfunction "10_10") (pintype "passive"))
    )
    (net (code "47") (name "unconnected-(U6-(3.3V)_T2C2{slash}MOSI1{slash}SMBAI1{slash}PB5-Pad41)") (class "Default")
      (node (ref "U6") (pin "41") (pinfunction "(3.3V)_T2C2/MOSI1/SMBAI1/PB5_41") (pintype "bidirectional"))
    )
    (net (code "48") (name "unconnected-(U6-CK3{slash}T1BKIN{slash}NSS2{slash}PB12-Pad25)") (class "Default")
      (node (ref "U6") (pin "25") (pinfunction "CK3/T1BKIN/NSS2/PB12_25") (pintype "bidirectional"))
    )
    (net (code "49") (name "unconnected-(U6-CTS3{slash}T1C1N{slash}SCK2{slash}PB13-Pad26)") (class "Default")
      (node (ref "U6") (pin "26") (pinfunction "CTS3/T1C1N/SCK2/PB13_26") (pintype "bidirectional"))
    )
    (net (code "50") (name "unconnected-(U6-PA4{slash}ADC4{slash}NSS1{slash}CK2_(3.3V)-Pad14)") (class "Default")
      (node (ref "U6") (pin "14") (pinfunction "PA4/ADC4/NSS1/CK2_(3.3V)_14") (pintype "bidirectional"))
    )
    (net (code "51") (name "unconnected-(U6-PA5{slash}ADC5{slash}SCK1_(3.3V)-Pad15)") (class "Default")
      (node (ref "U6") (pin "15") (pinfunction "PA5/ADC5/SCK1_(3.3V)_15") (pintype "bidirectional"))
    )
    (net (code "52") (name "unconnected-(U6-PA15{slash}JTDI{slash}NSS1{slash}T2C1E-Pad38)") (class "Default")
      (node (ref "U6") (pin "38") (pinfunction "PA15/JTDI/NSS1/T2C1E_38") (pintype "bidirectional"))
    )
    (net (code "53") (name "unconnected-(U6-RTS3{slash}T1C2N{slash}MISO2{slash}PB14-Pad27)") (class "Default")
      (node (ref "U6") (pin "27") (pinfunction "RTS3/T1C2N/MISO2/PB14_27") (pintype "bidirectional"))
    )
    (net (code "54") (name "unconnected-(U6-T1C3N{slash}MOSI2{slash}PB15-Pad28)") (class "Default")
      (node (ref "U6") (pin "28") (pinfunction "T1C3N/MOSI2/PB15_28") (pintype "bidirectional"))
    )
    (net (code "55") (name "unconnected-(U6-T2C2{slash}SCK1{slash}JTD0{slash}PB3-Pad39)") (class "Default")
      (node (ref "U6") (pin "39") (pinfunction "T2C2/SCK1/JTD0/PB3_39") (pintype "bidirectional"))
    )
    (net (code "56") (name "unconnected-(U6-T2C3N{slash}TX3{slash}SCL2{slash}PB10-Pad21)") (class "Default")
      (node (ref "U6") (pin "21") (pinfunction "T2C3N/TX3/SCL2/PB10_21") (pintype "bidirectional"))
    )
    (net (code "57") (name "unconnected-(U6-T2C4N{slash}RX3{slash}SDA2{slash}PB11-Pad22)") (class "Default")
      (node (ref "U6") (pin "22") (pinfunction "T2C4N/RX3/SDA2/PB11_22") (pintype "bidirectional"))
    )
    (net (code "58") (name "unconnected-(U6-T3C1{slash}MISO1{slash}JTRST{slash}PB4-Pad40)") (class "Default")
      (node (ref "U6") (pin "40") (pinfunction "T3C1/MISO1/JTRST/PB4_40") (pintype "bidirectional"))
    )
    (net (code "59") (name "unconnected-(USB1-SBUS1-PadA8)") (class "Default")
      (node (ref "USB1") (pin "A8") (pinfunction "SBUS1_A8") (pintype "passive"))
    )
    (net (code "60") (name "unconnected-(USB1-SBUS2-PadB8)") (class "Default")
      (node (ref "USB1") (pin "B8") (pinfunction "SBUS2_B8") (pintype "passive"))
    )
  )
)
